# WindSpeed.net
KiCad netlist of a schematic drawn in Altium Designer
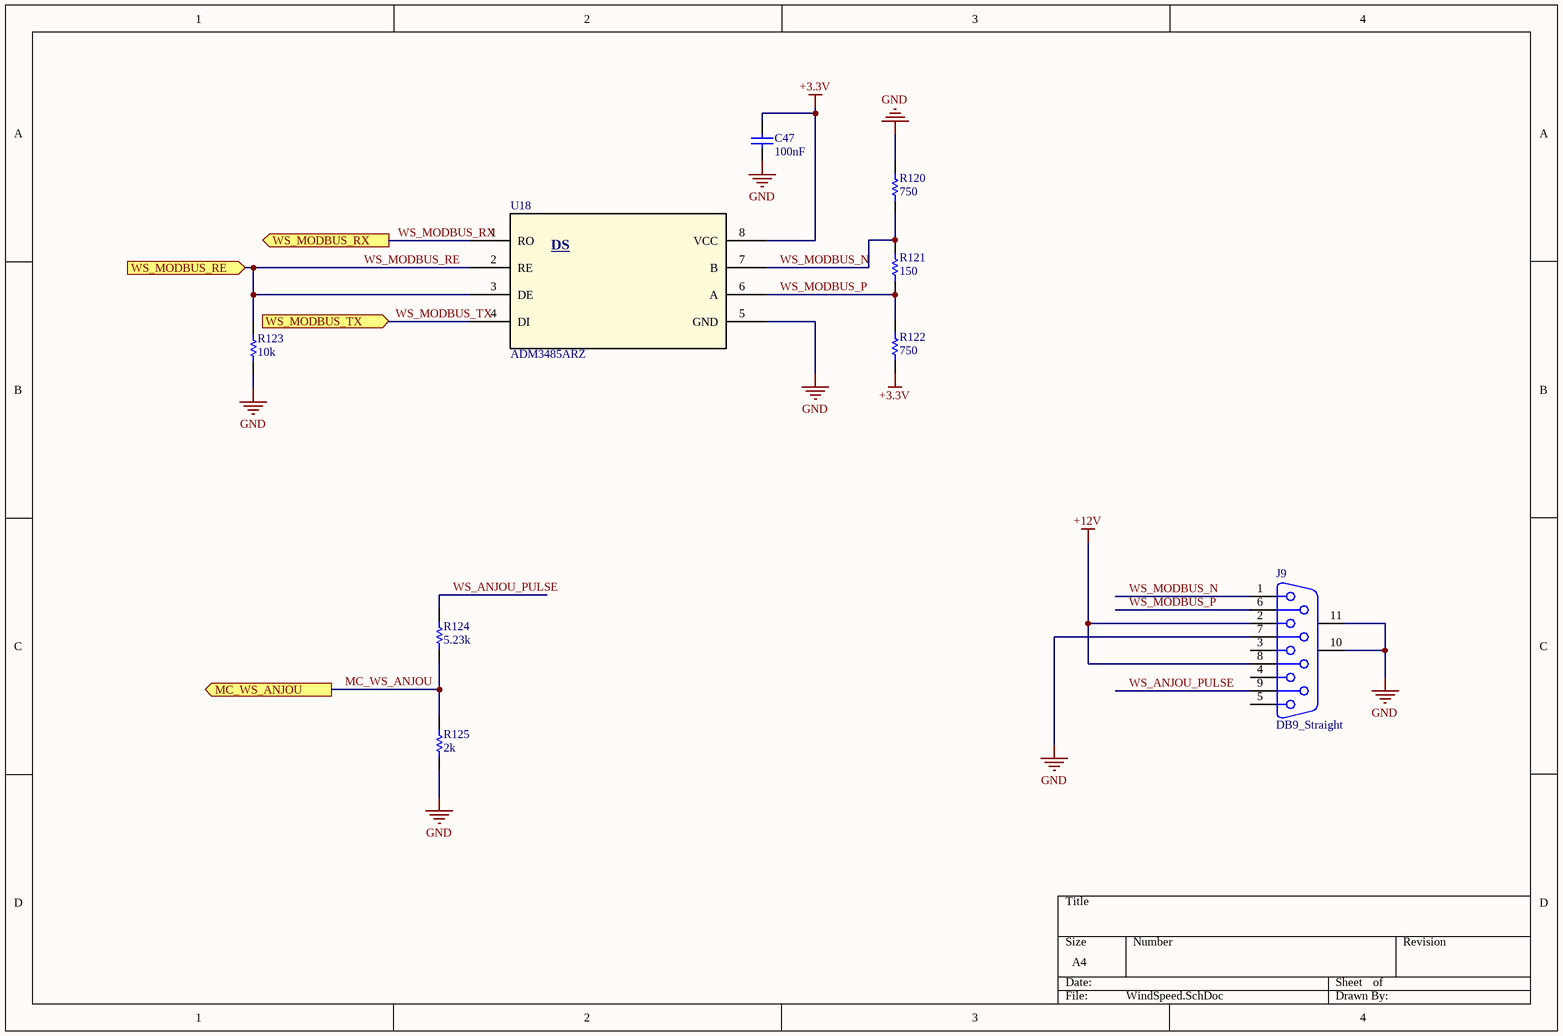
[diagram p0: WindSpeed.SchDoc]

(export (version "E")
  (design (tool "Eeschema 10.0.6"))
  (components
    (comp (ref "C47")
      (value "100nF")
      (footprint "C-805")
      (description "Capacitor")
      (fields (field (name "Comment") "C-805") (field (name "PUBLISHER") "Altium Limited"))
      (libsource (lib "AfraLIB") (part "C-805"))
    )
    (comp (ref "J9")
      (value "DB9_Straight")
      (footprint "DB9_Straight")
      (description "Receptacle Assembly, 9 Position, Right Angle")
      (fields (field (name "PUBLISHER") "Altium Limited"))
      (libsource (lib "AfraLIB") (part "DB9_Straight"))
    )
    (comp (ref "R120")
      (value "750")
      (footprint "R-805")
      (description "Resistor")
      (fields (field (name "Comment") "R-805"))
      (libsource (lib "AfraLIB") (part "R-805"))
    )
    (comp (ref "R121")
      (value "150")
      (footprint "R-805")
      (description "Resistor")
      (fields (field (name "Comment") "R-805"))
      (libsource (lib "AfraLIB") (part "R-805"))
    )
    (comp (ref "R122")
      (value "750")
      (footprint "R-805")
      (description "Resistor")
      (fields (field (name "Comment") "R-805"))
      (libsource (lib "AfraLIB") (part "R-805"))
    )
    (comp (ref "R123")
      (value "10k")
      (footprint "R-805")
      (description "Resistor")
      (fields (field (name "Comment") "R-805"))
      (libsource (lib "AfraLIB") (part "R-805"))
    )
    (comp (ref "R124")
      (value "5.23k")
      (footprint "R-805")
      (description "Resistor")
      (fields (field (name "Comment") "R-805"))
      (libsource (lib "AfraLIB") (part "R-805"))
    )
    (comp (ref "R125")
      (value "2k")
      (footprint "R-805")
      (description "Resistor")
      (fields (field (name "Comment") "R-805"))
      (libsource (lib "AfraLIB") (part "R-805"))
    )
    (comp (ref "U18")
      (value "ADM3485ARZ")
      (footprint "R_8")
      (description "No Description Available")
      (fields (field (name "COPYRIGHT") "Copyright (C) 2018 Accelerated Designs. All rights reserved"))
      (libsource (lib "AfraLIB") (part "ADM3485ARZ"))
    )
  )
  (nets
    (net (code "1") (name "+3.3V") (class "Default")
      (node (ref "C47") (pin "2") (pinfunction "2_2") (pintype "passive"))
      (node (ref "R122") (pin "1") (pinfunction "1_1") (pintype "passive"))
      (node (ref "U18") (pin "8") (pinfunction "VCC_8") (pintype "passive"))
    )
    (net (code "2") (name "+12V") (class "Default")
      (node (ref "J9") (pin "2") (pinfunction "2_2") (pintype "passive"))
      (node (ref "J9") (pin "8") (pinfunction "8_8") (pintype "passive"))
    )
    (net (code "3") (name "/MC_WS_ANJOU") (class "Default")
      (node (ref "R124") (pin "1") (pinfunction "1_1") (pintype "passive"))
      (node (ref "R125") (pin "2") (pinfunction "2_2") (pintype "passive"))
    )
    (net (code "4") (name "/WS_ANJOU_PULSE") (class "Default")
      (node (ref "J9") (pin "9") (pinfunction "9_9") (pintype "passive"))
      (node (ref "R124") (pin "2") (pinfunction "2_2") (pintype "passive"))
    )
    (net (code "5") (name "/WS_MODBUS_N") (class "Default")
      (node (ref "J9") (pin "1") (pinfunction "1_1") (pintype "passive"))
      (node (ref "R120") (pin "1") (pinfunction "1_1") (pintype "passive"))
      (node (ref "R121") (pin "2") (pinfunction "2_2") (pintype "passive"))
      (node (ref "U18") (pin "7") (pinfunction "B_7") (pintype "passive"))
    )
    (net (code "6") (name "/WS_MODBUS_P") (class "Default")
      (node (ref "J9") (pin "6") (pinfunction "6_6") (pintype "passive"))
      (node (ref "R121") (pin "1") (pinfunction "1_1") (pintype "passive"))
      (node (ref "R122") (pin "2") (pinfunction "2_2") (pintype "passive"))
      (node (ref "U18") (pin "6") (pinfunction "A_6") (pintype "passive"))
    )
    (net (code "7") (name "/WS_MODBUS_RE") (class "Default")
      (node (ref "R123") (pin "2") (pinfunction "2_2") (pintype "passive"))
      (node (ref "U18") (pin "2") (pinfunction "RE_2") (pintype "passive"))
      (node (ref "U18") (pin "3") (pinfunction "DE_3") (pintype "passive"))
    )
    (net (code "8") (name "/WS_MODBUS_RX") (class "Default")
      (node (ref "U18") (pin "1") (pinfunction "RO_1") (pintype "passive"))
    )
    (net (code "9") (name "/WS_MODBUS_TX") (class "Default")
      (node (ref "U18") (pin "4") (pinfunction "DI_4") (pintype "passive"))
    )
    (net (code "10") (name "GND") (class "Default")
      (node (ref "C47") (pin "1") (pinfunction "1_1") (pintype "passive"))
      (node (ref "J9") (pin "10") (pinfunction "MH1_10") (pintype "passive"))
      (node (ref "J9") (pin "11") (pinfunction "MH2_11") (pintype "passive"))
      (node (ref "J9") (pin "7") (pinfunction "7_7") (pintype "passive"))
      (node (ref "R120") (pin "2") (pinfunction "2_2") (pintype "passive"))
      (node (ref "R123") (pin "1") (pinfunction "1_1") (pintype "passive"))
      (node (ref "R125") (pin "1") (pinfunction "1_1") (pintype "passive"))
      (node (ref "U18") (pin "5") (pinfunction "GND_5") (pintype "passive"))
    )
    (net (code "11") (name "unconnected-(J9-Pad3)") (class "Default")
      (node (ref "J9") (pin "3") (pinfunction "3_3") (pintype "passive"))
    )
    (net (code "12") (name "unconnected-(J9-Pad4)") (class "Default")
      (node (ref "J9") (pin "4") (pinfunction "4_4") (pintype "passive"))
    )
    (net (code "13") (name "unconnected-(J9-Pad5)") (class "Default")
      (node (ref "J9") (pin "5") (pinfunction "5_5") (pintype "passive"))
    )
  )
)
